# 04_-BUTTON.net
KiCad netlist of a schematic drawn in Altium Designer
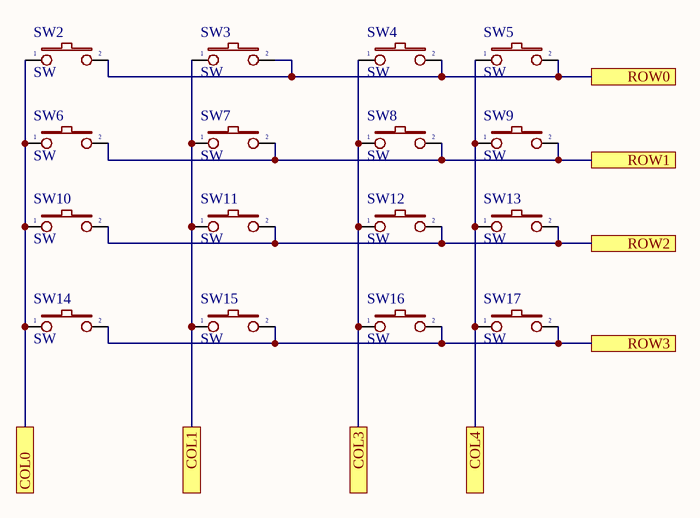
[diagram p0: [04]-BUTTON.SchDoc]

(export (version "E")
  (design (tool "Eeschema 10.0.6"))
  (components
    (comp (ref "SW2")
      (value "SW")
      (footprint "SW2")
      (description "Switch button 2 pin")
      (libsource (lib "My Library") (part "SW2"))
    )
    (comp (ref "SW3")
      (value "SW")
      (footprint "SW2")
      (description "Switch button 2 pin")
      (libsource (lib "My Library") (part "SW2"))
    )
    (comp (ref "SW4")
      (value "SW")
      (footprint "SW2")
      (description "Switch button 2 pin")
      (libsource (lib "My Library") (part "SW2"))
    )
    (comp (ref "SW5")
      (value "SW")
      (footprint "SW2")
      (description "Switch button 2 pin")
      (libsource (lib "My Library") (part "SW2"))
    )
    (comp (ref "SW6")
      (value "SW")
      (footprint "SW2")
      (description "Switch button 2 pin")
      (libsource (lib "My Library") (part "SW2"))
    )
    (comp (ref "SW7")
      (value "SW")
      (footprint "SW2")
      (description "Switch button 2 pin")
      (libsource (lib "My Library") (part "SW2"))
    )
    (comp (ref "SW8")
      (value "SW")
      (footprint "SW2")
      (description "Switch button 2 pin")
      (libsource (lib "My Library") (part "SW2"))
    )
    (comp (ref "SW9")
      (value "SW")
      (footprint "SW2")
      (description "Switch button 2 pin")
      (libsource (lib "My Library") (part "SW2"))
    )
    (comp (ref "SW10")
      (value "SW")
      (footprint "SW2")
      (description "Switch button 2 pin")
      (libsource (lib "My Library") (part "SW2"))
    )
    (comp (ref "SW11")
      (value "SW")
      (footprint "SW2")
      (description "Switch button 2 pin")
      (libsource (lib "My Library") (part "SW2"))
    )
    (comp (ref "SW12")
      (value "SW")
      (footprint "SW2")
      (description "Switch button 2 pin")
      (libsource (lib "My Library") (part "SW2"))
    )
    (comp (ref "SW13")
      (value "SW")
      (footprint "SW2")
      (description "Switch button 2 pin")
      (libsource (lib "My Library") (part "SW2"))
    )
    (comp (ref "SW14")
      (value "SW")
      (footprint "SW2")
      (description "Switch button 2 pin")
      (libsource (lib "My Library") (part "SW2"))
    )
    (comp (ref "SW15")
      (value "SW")
      (footprint "SW2")
      (description "Switch button 2 pin")
      (libsource (lib "My Library") (part "SW2"))
    )
    (comp (ref "SW16")
      (value "SW")
      (footprint "SW2")
      (description "Switch button 2 pin")
      (libsource (lib "My Library") (part "SW2"))
    )
    (comp (ref "SW17")
      (value "SW")
      (footprint "SW2")
      (description "Switch button 2 pin")
      (libsource (lib "My Library") (part "SW2"))
    )
  )
  (nets
    (net (code "1") (name "/COL0") (class "Default")
      (node (ref "SW10") (pin "1") (pinfunction "1_1") (pintype "passive"))
      (node (ref "SW14") (pin "1") (pinfunction "1_1") (pintype "passive"))
      (node (ref "SW2") (pin "1") (pinfunction "1_1") (pintype "passive"))
      (node (ref "SW6") (pin "1") (pinfunction "1_1") (pintype "passive"))
    )
    (net (code "2") (name "/COL1") (class "Default")
      (node (ref "SW11") (pin "1") (pinfunction "1_1") (pintype "passive"))
      (node (ref "SW15") (pin "1") (pinfunction "1_1") (pintype "passive"))
      (node (ref "SW3") (pin "1") (pinfunction "1_1") (pintype "passive"))
      (node (ref "SW7") (pin "1") (pinfunction "1_1") (pintype "passive"))
    )
    (net (code "3") (name "/COL3") (class "Default")
      (node (ref "SW12") (pin "1") (pinfunction "1_1") (pintype "passive"))
      (node (ref "SW16") (pin "1") (pinfunction "1_1") (pintype "passive"))
      (node (ref "SW4") (pin "1") (pinfunction "1_1") (pintype "passive"))
      (node (ref "SW8") (pin "1") (pinfunction "1_1") (pintype "passive"))
    )
    (net (code "4") (name "/COL4") (class "Default")
      (node (ref "SW13") (pin "1") (pinfunction "1_1") (pintype "passive"))
      (node (ref "SW17") (pin "1") (pinfunction "1_1") (pintype "passive"))
      (node (ref "SW5") (pin "1") (pinfunction "1_1") (pintype "passive"))
      (node (ref "SW9") (pin "1") (pinfunction "1_1") (pintype "passive"))
    )
    (net (code "5") (name "/ROW0") (class "Default")
      (node (ref "SW2") (pin "2") (pinfunction "2_2") (pintype "passive"))
      (node (ref "SW3") (pin "2") (pinfunction "2_2") (pintype "passive"))
      (node (ref "SW4") (pin "2") (pinfunction "2_2") (pintype "passive"))
      (node (ref "SW5") (pin "2") (pinfunction "2_2") (pintype "passive"))
    )
    (net (code "6") (name "/ROW1") (class "Default")
      (node (ref "SW6") (pin "2") (pinfunction "2_2") (pintype "passive"))
      (node (ref "SW7") (pin "2") (pinfunction "2_2") (pintype "passive"))
      (node (ref "SW8") (pin "2") (pinfunction "2_2") (pintype "passive"))
      (node (ref "SW9") (pin "2") (pinfunction "2_2") (pintype "passive"))
    )
    (net (code "7") (name "/ROW2") (class "Default")
      (node (ref "SW10") (pin "2") (pinfunction "2_2") (pintype "passive"))
      (node (ref "SW11") (pin "2") (pinfunction "2_2") (pintype "passive"))
      (node (ref "SW12") (pin "2") (pinfunction "2_2") (pintype "passive"))
      (node (ref "SW13") (pin "2") (pinfunction "2_2") (pintype "passive"))
    )
    (net (code "8") (name "/ROW3") (class "Default")
      (node (ref "SW14") (pin "2") (pinfunction "2_2") (pintype "passive"))
      (node (ref "SW15") (pin "2") (pinfunction "2_2") (pintype "passive"))
      (node (ref "SW16") (pin "2") (pinfunction "2_2") (pintype "passive"))
      (node (ref "SW17") (pin "2") (pinfunction "2_2") (pintype "passive"))
    )
  )
)
